# thermistor.net
KiCad netlist of a schematic drawn in EAGLE
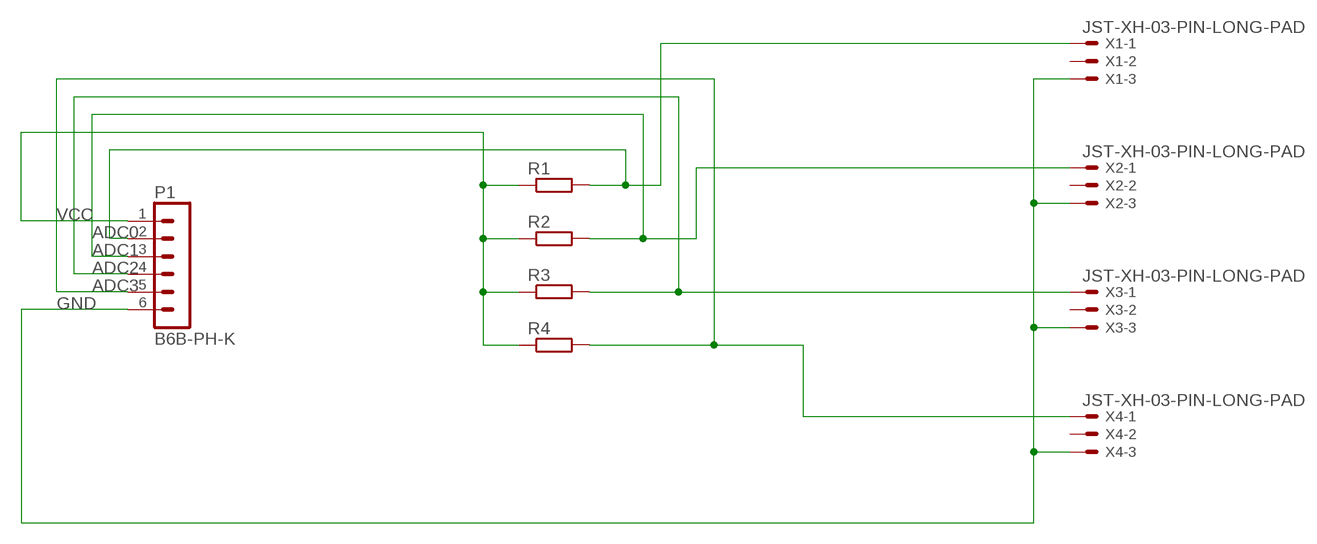
[diagram p0: schematic, sheet 1]

(export (version "E")
  (design (tool "Eeschema 10.0.6"))
  (components
    (comp (ref "P1")
      (value "B6B-PH-K")
      (footprint "eagle-import:B6B-PH-K")
      (libsource (lib "eagle-import") (part "B6B-PH-K"))
    )
    (comp (ref "R1")
      (value "R-EU_0207/10")
      (footprint "eagle-import:0207_10")
      (libsource (lib "eagle-import") (part "R-EU_0207/10"))
    )
    (comp (ref "R2")
      (value "R-EU_0207/10")
      (footprint "eagle-import:0207_10")
      (libsource (lib "eagle-import") (part "R-EU_0207/10"))
    )
    (comp (ref "R3")
      (value "R-EU_0207/10")
      (footprint "eagle-import:0207_10")
      (libsource (lib "eagle-import") (part "R-EU_0207/10"))
    )
    (comp (ref "R4")
      (value "R-EU_0207/10")
      (footprint "eagle-import:0207_10")
      (libsource (lib "eagle-import") (part "R-EU_0207/10"))
    )
    (comp (ref "X1")
      (value "JST-XH-03-PIN-LONG-PAD")
      (footprint "eagle-import:JST-XH-03-PACKAGE-LONG-PAD")
      (libsource (lib "eagle-import") (part "JST-XH-03-PIN-LONG-PAD"))
    )
    (comp (ref "X2")
      (value "JST-XH-03-PIN-LONG-PAD")
      (footprint "eagle-import:JST-XH-03-PACKAGE-LONG-PAD")
      (libsource (lib "eagle-import") (part "JST-XH-03-PIN-LONG-PAD"))
    )
    (comp (ref "X3")
      (value "JST-XH-03-PIN-LONG-PAD")
      (footprint "eagle-import:JST-XH-03-PACKAGE-LONG-PAD")
      (libsource (lib "eagle-import") (part "JST-XH-03-PIN-LONG-PAD"))
    )
    (comp (ref "X4")
      (value "JST-XH-03-PIN-LONG-PAD")
      (footprint "eagle-import:JST-XH-03-PACKAGE-LONG-PAD")
      (libsource (lib "eagle-import") (part "JST-XH-03-PIN-LONG-PAD"))
    )
  )
  (nets
    (net (code "1") (name "/ADC0") (class "Default")
      (node (ref "P1") (pin "2") (pinfunction "2_2") (pintype "passive"))
      (node (ref "R1") (pin "2") (pinfunction "2_2") (pintype "passive"))
      (node (ref "X1") (pin "1") (pinfunction "S_1") (pintype "passive"))
    )
    (net (code "2") (name "/ADC1") (class "Default")
      (node (ref "P1") (pin "3") (pinfunction "3_3") (pintype "passive"))
      (node (ref "R2") (pin "2") (pinfunction "2_2") (pintype "passive"))
      (node (ref "X2") (pin "1") (pinfunction "S_1") (pintype "passive"))
    )
    (net (code "3") (name "/ADC2") (class "Default")
      (node (ref "P1") (pin "4") (pinfunction "4_4") (pintype "passive"))
      (node (ref "R3") (pin "2") (pinfunction "2_2") (pintype "passive"))
      (node (ref "X3") (pin "1") (pinfunction "S_1") (pintype "passive"))
    )
    (net (code "4") (name "/ADC3") (class "Default")
      (node (ref "P1") (pin "5") (pinfunction "5_5") (pintype "passive"))
      (node (ref "R4") (pin "2") (pinfunction "2_2") (pintype "passive"))
      (node (ref "X4") (pin "1") (pinfunction "S_1") (pintype "passive"))
    )
    (net (code "5") (name "/GND") (class "Default")
      (node (ref "P1") (pin "6") (pinfunction "6_6") (pintype "passive"))
      (node (ref "X1") (pin "3") (pinfunction "S_3") (pintype "passive"))
      (node (ref "X2") (pin "3") (pinfunction "S_3") (pintype "passive"))
      (node (ref "X3") (pin "3") (pinfunction "S_3") (pintype "passive"))
      (node (ref "X4") (pin "3") (pinfunction "S_3") (pintype "passive"))
    )
    (net (code "6") (name "/VCC") (class "Default")
      (node (ref "P1") (pin "1") (pinfunction "1_1") (pintype "passive"))
      (node (ref "R1") (pin "1") (pinfunction "1_1") (pintype "passive"))
      (node (ref "R2") (pin "1") (pinfunction "1_1") (pintype "passive"))
      (node (ref "R3") (pin "1") (pinfunction "1_1") (pintype "passive"))
      (node (ref "R4") (pin "1") (pinfunction "1_1") (pintype "passive"))
    )
    (net (code "7") (name "unconnected-(X1B-S-Pad2)") (class "Default")
      (node (ref "X1") (pin "2") (pinfunction "S_2") (pintype "passive"))
    )
    (net (code "8") (name "unconnected-(X2B-S-Pad2)") (class "Default")
      (node (ref "X2") (pin "2") (pinfunction "S_2") (pintype "passive"))
    )
    (net (code "9") (name "unconnected-(X3B-S-Pad2)") (class "Default")
      (node (ref "X3") (pin "2") (pinfunction "S_2") (pintype "passive"))
    )
    (net (code "10") (name "unconnected-(X4B-S-Pad2)") (class "Default")
      (node (ref "X4") (pin "2") (pinfunction "S_2") (pintype "passive"))
    )
  )
)
